# hail-met-v1.net
KiCad netlist of a schematic drawn in EAGLE
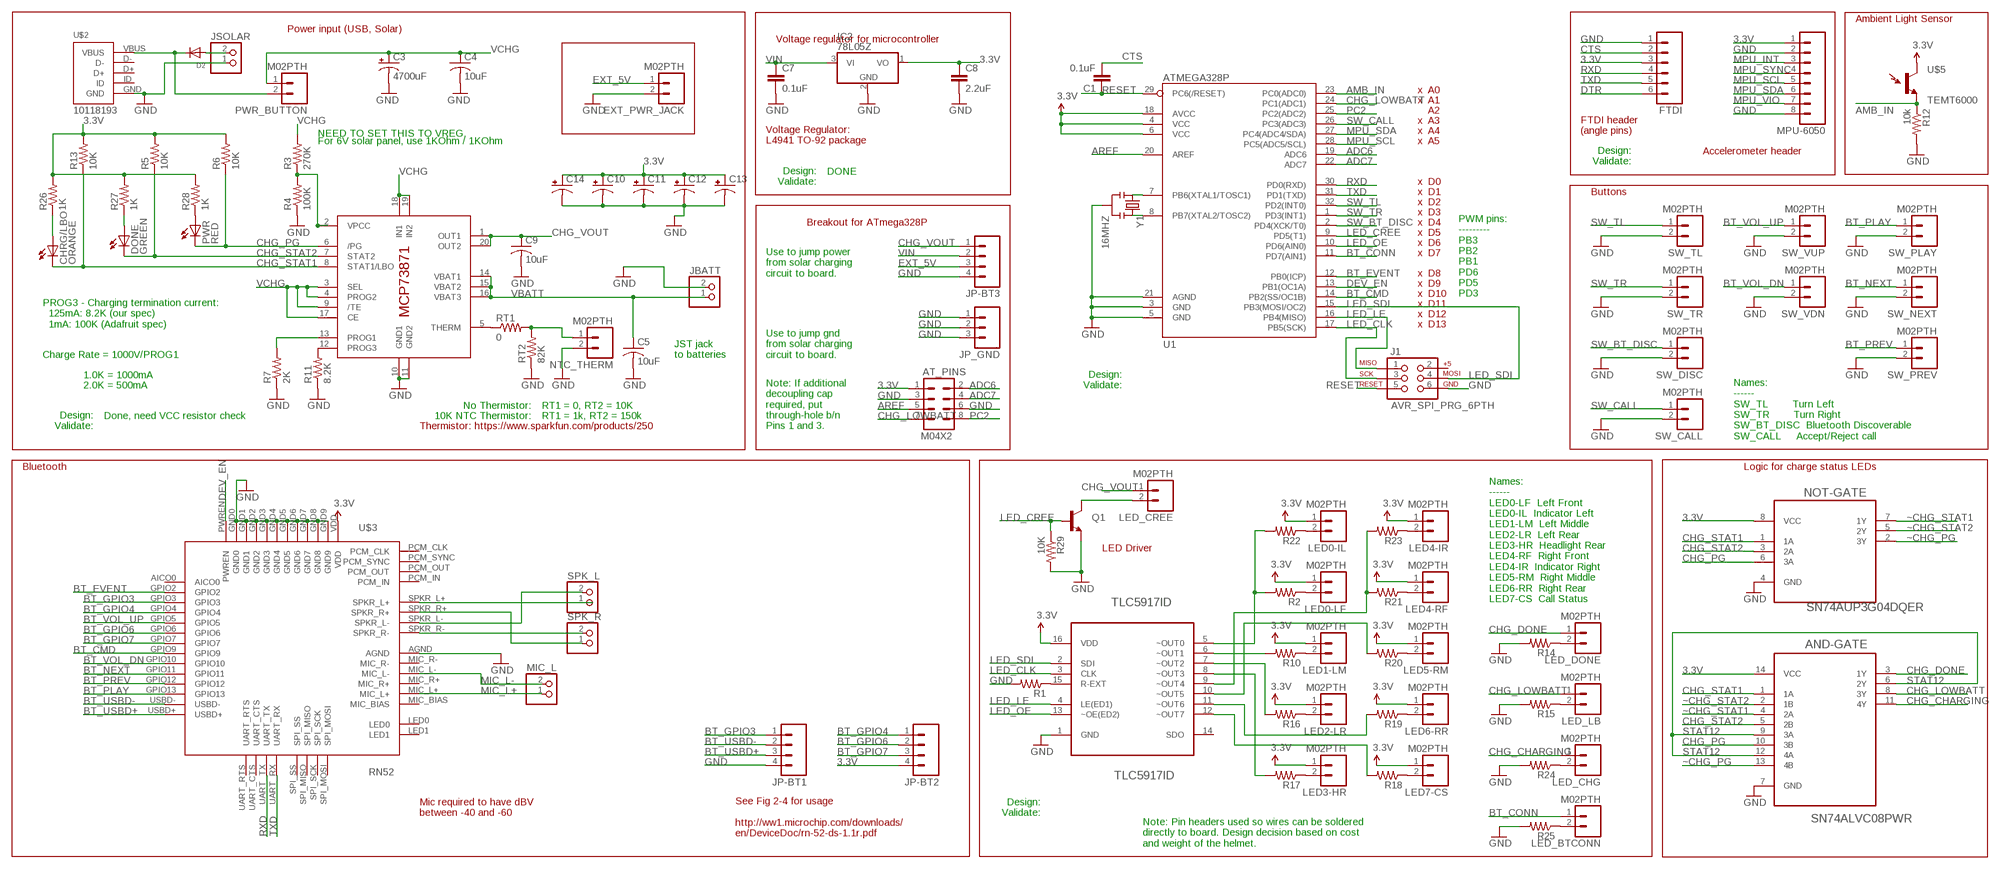
[diagram p0: schematic, sheet 1]

(export (version "E")
  (design (tool "Eeschema 10.0.6"))
  (components
    (comp (ref "AND-GATE")
      (value "SN74ALVC08PWR")
      (footprint "eagle-import:SOP65P640X120-14N")
      (libsource (lib "eagle-import") (part "SN74ALVC08PWR"))
    )
    (comp (ref "AT_PINS")
      (value "M04X2")
      (footprint "eagle-import:2X4")
      (libsource (lib "eagle-import") (part "M04X2"))
    )
    (comp (ref "C1")
      (value "0.1uF")
      (footprint "eagle-import:0805")
      (libsource (lib "eagle-import") (part "CAP0805"))
    )
    (comp (ref "C3")
      (value "4700uF")
      (footprint "eagle-import:E5-13")
      (libsource (lib "eagle-import") (part "CPOL-USE5-13"))
    )
    (comp (ref "C4")
      (value "10uF")
      (footprint "eagle-import:C0805K")
      (libsource (lib "eagle-import") (part "C-USC0805K"))
    )
    (comp (ref "C5")
      (value "10uF")
      (footprint "eagle-import:C0805K")
      (libsource (lib "eagle-import") (part "rcl_C-USC0805K"))
    )
    (comp (ref "C7")
      (value "0.1uF")
      (footprint "eagle-import:0805")
      (libsource (lib "eagle-import") (part "CAP0805"))
    )
    (comp (ref "C8")
      (value "2.2uF")
      (footprint "eagle-import:0805")
      (libsource (lib "eagle-import") (part "CAP0805"))
    )
    (comp (ref "C9")
      (value "10uF")
      (footprint "eagle-import:C0805K")
      (libsource (lib "eagle-import") (part "C-USC0805K"))
    )
    (comp (ref "C10")
      (value "CAP_POLPTH1")
      (footprint "eagle-import:CPOL-RADIAL-100UF-25V")
      (libsource (lib "eagle-import") (part "CAP_POLPTH1"))
    )
    (comp (ref "C11")
      (value "CAP_POLPTH1")
      (footprint "eagle-import:CPOL-RADIAL-100UF-25V")
      (libsource (lib "eagle-import") (part "CAP_POLPTH1"))
    )
    (comp (ref "C12")
      (value "CAP_POLPTH1")
      (footprint "eagle-import:CPOL-RADIAL-100UF-25V")
      (libsource (lib "eagle-import") (part "CAP_POLPTH1"))
    )
    (comp (ref "C13")
      (value "CAP_POLPTH1")
      (footprint "eagle-import:CPOL-RADIAL-100UF-25V")
      (libsource (lib "eagle-import") (part "CAP_POLPTH1"))
    )
    (comp (ref "C14")
      (value "CAP_POLPTH1")
      (footprint "eagle-import:CPOL-RADIAL-100UF-25V")
      (libsource (lib "eagle-import") (part "CAP_POLPTH1"))
    )
    (comp (ref "CHRG/LBO")
      (value "ORANGE")
      (footprint "eagle-import:CHIP-LED0805")
      (libsource (lib "eagle-import") (part "LEDCHIP-LED0805"))
    )
    (comp (ref "D2")
      (value "DIODESOD-123")
      (footprint "eagle-import:SOD-123")
      (libsource (lib "eagle-import") (part "DIODESOD-123"))
    )
    (comp (ref "DONE")
      (value "GREEN")
      (footprint "eagle-import:CHIP-LED0805")
      (libsource (lib "eagle-import") (part "LEDCHIP-LED0805"))
    )
    (comp (ref "EXT_PWR_JACK")
      (value "M02PTH")
      (footprint "eagle-import:1X02")
      (libsource (lib "eagle-import") (part "M02PTH"))
    )
    (comp (ref "FTDI")
      (value "M06LOCK")
      (footprint "eagle-import:1X06_LOCK")
      (libsource (lib "eagle-import") (part "M06LOCK"))
    )
    (comp (ref "IC1")
      (value "MCP73871")
      (footprint "eagle-import:QFN20")
      (libsource (lib "eagle-import") (part "MCP73871"))
    )
    (comp (ref "IC2")
      (value "78L05Z")
      (footprint "eagle-import:TO92")
      (libsource (lib "eagle-import") (part "78ZL05"))
    )
    (comp (ref "J1")
      (value "AVR_SPI_PRG_6PTH")
      (footprint "eagle-import:2X3")
      (libsource (lib "eagle-import") (part "AVR_SPI_PRG_6PTH"))
    )
    (comp (ref "JBATT")
      (value "JST_2PIN-SMT")
      (footprint "eagle-import:JST-PH-2-SMT")
      (libsource (lib "eagle-import") (part "JST_2PIN-SMT"))
    )
    (comp (ref "JP-BT1")
      (value "M04LOCK")
      (footprint "eagle-import:1X04_LOCK")
      (libsource (lib "eagle-import") (part "M04LOCK"))
    )
    (comp (ref "JP-BT2")
      (value "M04LOCK")
      (footprint "eagle-import:1X04_LOCK")
      (libsource (lib "eagle-import") (part "M04LOCK"))
    )
    (comp (ref "JP-BT3")
      (value "M04LOCK")
      (footprint "eagle-import:1X04_LOCK")
      (libsource (lib "eagle-import") (part "M04LOCK"))
    )
    (comp (ref "JP_GND")
      (value "M03LOCK")
      (footprint "eagle-import:1X03_LOCK")
      (libsource (lib "eagle-import") (part "M03LOCK"))
    )
    (comp (ref "JSOLAR")
      (value "JST_2PIN-SMT")
      (footprint "eagle-import:JST-PH-2-SMT")
      (libsource (lib "eagle-import") (part "JST_2PIN-SMT"))
    )
    (comp (ref "LED0-IL")
      (value "M02PTH")
      (footprint "eagle-import:1X02")
      (libsource (lib "eagle-import") (part "M02PTH"))
    )
    (comp (ref "LED0-LF")
      (value "M02PTH")
      (footprint "eagle-import:1X02")
      (libsource (lib "eagle-import") (part "M02PTH"))
    )
    (comp (ref "LED1-LM")
      (value "M02PTH")
      (footprint "eagle-import:1X02")
      (libsource (lib "eagle-import") (part "M02PTH"))
    )
    (comp (ref "LED2-LR")
      (value "M02PTH")
      (footprint "eagle-import:1X02")
      (libsource (lib "eagle-import") (part "M02PTH"))
    )
    (comp (ref "LED3-HR")
      (value "M02PTH")
      (footprint "eagle-import:1X02")
      (libsource (lib "eagle-import") (part "M02PTH"))
    )
    (comp (ref "LED4-IR")
      (value "M02PTH")
      (footprint "eagle-import:1X02")
      (libsource (lib "eagle-import") (part "M02PTH"))
    )
    (comp (ref "LED4-RF")
      (value "M02PTH")
      (footprint "eagle-import:1X02")
      (libsource (lib "eagle-import") (part "M02PTH"))
    )
    (comp (ref "LED5-RM")
      (value "M02PTH")
      (footprint "eagle-import:1X02")
      (libsource (lib "eagle-import") (part "M02PTH"))
    )
    (comp (ref "LED6-RR")
      (value "M02PTH")
      (footprint "eagle-import:1X02")
      (libsource (lib "eagle-import") (part "M02PTH"))
    )
    (comp (ref "LED7-CS")
      (value "M02PTH")
      (footprint "eagle-import:1X02")
      (libsource (lib "eagle-import") (part "M02PTH"))
    )
    (comp (ref "LED_BTCONN")
      (value "M02PTH")
      (footprint "eagle-import:1X02")
      (libsource (lib "eagle-import") (part "M02PTH"))
    )
    (comp (ref "LED_CHG")
      (value "M02PTH")
      (footprint "eagle-import:1X02")
      (libsource (lib "eagle-import") (part "M02PTH"))
    )
    (comp (ref "LED_CREE")
      (value "M02PTH")
      (footprint "eagle-import:1X02")
      (libsource (lib "eagle-import") (part "M02PTH"))
    )
    (comp (ref "LED_DONE")
      (value "M02PTH")
      (footprint "eagle-import:1X02")
      (libsource (lib "eagle-import") (part "M02PTH"))
    )
    (comp (ref "LED_LB")
      (value "M02PTH")
      (footprint "eagle-import:1X02")
      (libsource (lib "eagle-import") (part "M02PTH"))
    )
    (comp (ref "MIC_L")
      (value "JST_2PIN-SMT")
      (footprint "eagle-import:JST-PH-2-SMT")
      (libsource (lib "eagle-import") (part "JST_2PIN-SMT"))
    )
    (comp (ref "MPU-6050")
      (value "M08LOCK")
      (footprint "eagle-import:1X08_LOCK")
      (libsource (lib "eagle-import") (part "M08LOCK"))
    )
    (comp (ref "NOT-GATE")
      (value "SN74AUP3G04DQER")
      (footprint "eagle-import:SON35P100X140X40-8N")
      (libsource (lib "eagle-import") (part "SN74AUP3G04DQER"))
    )
    (comp (ref "NTC_THERM")
      (value "M02PTH")
      (footprint "eagle-import:1X02")
      (libsource (lib "eagle-import") (part "M02PTH"))
    )
    (comp (ref "PWR")
      (value "RED")
      (footprint "eagle-import:CHIP-LED0805")
      (libsource (lib "eagle-import") (part "LEDCHIP-LED0805"))
    )
    (comp (ref "PWR_BUTTON")
      (value "M02PTH")
      (footprint "eagle-import:1X02")
      (libsource (lib "eagle-import") (part "M02PTH"))
    )
    (comp (ref "Q1")
      (value "TRANSISTOR_NPNSOT23-3")
      (footprint "eagle-import:SOT23-3")
      (libsource (lib "eagle-import") (part "TRANSISTOR_NPNSOT23-3"))
    )
    (comp (ref "R1")
      (value "RESISTOR0805-RES")
      (footprint "eagle-import:0805")
      (libsource (lib "eagle-import") (part "RESISTOR0805-RES"))
    )
    (comp (ref "R2")
      (value "RESISTOR0805-RES")
      (footprint "eagle-import:0805")
      (libsource (lib "eagle-import") (part "RESISTOR0805-RES"))
    )
    (comp (ref "R3")
      (value "270K")
      (footprint "eagle-import:0805")
      (libsource (lib "eagle-import") (part "RESISTOR0805-RES"))
    )
    (comp (ref "R4")
      (value "100K")
      (footprint "eagle-import:0805")
      (libsource (lib "eagle-import") (part "RESISTOR0805-RES"))
    )
    (comp (ref "R5")
      (value "10K")
      (footprint "eagle-import:0805")
      (libsource (lib "eagle-import") (part "RESISTOR0805-RES"))
    )
    (comp (ref "R6")
      (value "10K")
      (footprint "eagle-import:0805")
      (libsource (lib "eagle-import") (part "RESISTOR0805-RES"))
    )
    (comp (ref "R7")
      (value "2K")
      (footprint "eagle-import:0805")
      (libsource (lib "eagle-import") (part "RESISTOR0805-RES"))
    )
    (comp (ref "R10")
      (value "RESISTOR0805-RES")
      (footprint "eagle-import:0805")
      (libsource (lib "eagle-import") (part "RESISTOR0805-RES"))
    )
    (comp (ref "R11")
      (value "8.2K")
      (footprint "eagle-import:0805")
      (libsource (lib "eagle-import") (part "RESISTOR0805-RES"))
    )
    (comp (ref "R12")
      (value "10k")
      (footprint "eagle-import:0805")
      (libsource (lib "eagle-import") (part "RESISTOR0805-RES"))
    )
    (comp (ref "R13")
      (value "10K")
      (footprint "eagle-import:0805")
      (libsource (lib "eagle-import") (part "RESISTOR0805-RES"))
    )
    (comp (ref "R14")
      (value "RESISTOR0805-RES")
      (footprint "eagle-import:0805")
      (libsource (lib "eagle-import") (part "RESISTOR0805-RES"))
    )
    (comp (ref "R15")
      (value "RESISTOR0805-RES")
      (footprint "eagle-import:0805")
      (libsource (lib "eagle-import") (part "RESISTOR0805-RES"))
    )
    (comp (ref "R16")
      (value "RESISTOR0805-RES")
      (footprint "eagle-import:0805")
      (libsource (lib "eagle-import") (part "RESISTOR0805-RES"))
    )
    (comp (ref "R17")
      (value "RESISTOR0805-RES")
      (footprint "eagle-import:0805")
      (libsource (lib "eagle-import") (part "RESISTOR0805-RES"))
    )
    (comp (ref "R18")
      (value "RESISTOR0805-RES")
      (footprint "eagle-import:0805")
      (libsource (lib "eagle-import") (part "RESISTOR0805-RES"))
    )
    (comp (ref "R19")
      (value "RESISTOR0805-RES")
      (footprint "eagle-import:0805")
      (libsource (lib "eagle-import") (part "RESISTOR0805-RES"))
    )
    (comp (ref "R20")
      (value "RESISTOR0805-RES")
      (footprint "eagle-import:0805")
      (libsource (lib "eagle-import") (part "RESISTOR0805-RES"))
    )
    (comp (ref "R21")
      (value "RESISTOR0805-RES")
      (footprint "eagle-import:0805")
      (libsource (lib "eagle-import") (part "RESISTOR0805-RES"))
    )
    (comp (ref "R22")
      (value "RESISTOR0805-RES")
      (footprint "eagle-import:0805")
      (libsource (lib "eagle-import") (part "RESISTOR0805-RES"))
    )
    (comp (ref "R23")
      (value "RESISTOR0805-RES")
      (footprint "eagle-import:0805")
      (libsource (lib "eagle-import") (part "RESISTOR0805-RES"))
    )
    (comp (ref "R24")
      (value "RESISTOR0805-RES")
      (footprint "eagle-import:0805")
      (libsource (lib "eagle-import") (part "RESISTOR0805-RES"))
    )
    (comp (ref "R25")
      (value "RESISTOR0805-RES")
      (footprint "eagle-import:0805")
      (libsource (lib "eagle-import") (part "RESISTOR0805-RES"))
    )
    (comp (ref "R26")
      (value "1K")
      (footprint "eagle-import:0805")
      (libsource (lib "eagle-import") (part "RESISTOR0805-RES"))
    )
    (comp (ref "R27")
      (value "1K")
      (footprint "eagle-import:0805")
      (libsource (lib "eagle-import") (part "RESISTOR0805-RES"))
    )
    (comp (ref "R28")
      (value "1K")
      (footprint "eagle-import:0805")
      (libsource (lib "eagle-import") (part "RESISTOR0805-RES"))
    )
    (comp (ref "R29")
      (value "10K")
      (footprint "eagle-import:0805")
      (libsource (lib "eagle-import") (part "RESISTOR0805-RES"))
    )
    (comp (ref "RT1")
      (value "0")
      (footprint "eagle-import:0805")
      (libsource (lib "eagle-import") (part "RESISTOR0805-RES"))
    )
    (comp (ref "RT2")
      (value "82K")
      (footprint "eagle-import:0805")
      (libsource (lib "eagle-import") (part "RESISTOR0805-RES"))
    )
    (comp (ref "SPK_L")
      (value "JST_2PIN-SMT")
      (footprint "eagle-import:JST-PH-2-SMT")
      (libsource (lib "eagle-import") (part "JST_2PIN-SMT"))
    )
    (comp (ref "SPK_R")
      (value "JST_2PIN-SMT")
      (footprint "eagle-import:JST-PH-2-SMT")
      (libsource (lib "eagle-import") (part "JST_2PIN-SMT"))
    )
    (comp (ref "SW_CALL")
      (value "M02PTH")
      (footprint "eagle-import:1X02")
      (libsource (lib "eagle-import") (part "M02PTH"))
    )
    (comp (ref "SW_DISC")
      (value "M02PTH")
      (footprint "eagle-import:1X02")
      (libsource (lib "eagle-import") (part "M02PTH"))
    )
    (comp (ref "SW_NEXT")
      (value "M02PTH")
      (footprint "eagle-import:1X02")
      (libsource (lib "eagle-import") (part "M02PTH"))
    )
    (comp (ref "SW_PLAY")
      (value "M02PTH")
      (footprint "eagle-import:1X02")
      (libsource (lib "eagle-import") (part "M02PTH"))
    )
    (comp (ref "SW_PREV")
      (value "M02PTH")
      (footprint "eagle-import:1X02")
      (libsource (lib "eagle-import") (part "M02PTH"))
    )
    (comp (ref "SW_TL")
      (value "M02PTH")
      (footprint "eagle-import:1X02")
      (libsource (lib "eagle-import") (part "M02PTH"))
    )
    (comp (ref "SW_TR")
      (value "M02PTH")
      (footprint "eagle-import:1X02")
      (libsource (lib "eagle-import") (part "M02PTH"))
    )
    (comp (ref "SW_VDN")
      (value "M02PTH")
      (footprint "eagle-import:1X02")
      (libsource (lib "eagle-import") (part "M02PTH"))
    )
    (comp (ref "SW_VUP")
      (value "M02PTH")
      (footprint "eagle-import:1X02")
      (libsource (lib "eagle-import") (part "M02PTH"))
    )
    (comp (ref "TLC5917ID")
      (value "TLC5917ID")
      (footprint "eagle-import:SOIC127P600X175-16N")
      (libsource (lib "eagle-import") (part "TLC5917ID"))
    )
    (comp (ref "U$2")
      (value "10118193")
      (footprint "eagle-import:10118193")
      (libsource (lib "eagle-import") (part "10118193"))
    )
    (comp (ref "U$3")
      (value "RN52")
      (footprint "eagle-import:RN52")
      (libsource (lib "eagle-import") (part "RN52"))
    )
    (comp (ref "U$5")
      (value "TEMT6000")
      (footprint "eagle-import:TEMT6000-SEN")
      (libsource (lib "eagle-import") (part "TEMT6000"))
    )
    (comp (ref "U1")
      (value "ATMEGA328P")
      (footprint "eagle-import:TQFP32-08")
      (libsource (lib "eagle-import") (part "ATMEGA328_SMT"))
    )
    (comp (ref "Y1")
      (value "16MHZ")
      (footprint "eagle-import:RESONATOR-SMD")
      (libsource (lib "eagle-import") (part "RESONATOR16MHZ"))
    )
  )
  (nets
    (net (code "1") (name "/ADC6") (class "Default")
      (node (ref "AT_PINS") (pin "2") (pinfunction "2_2") (pintype "passive"))
      (node (ref "U1") (pin "19") (pinfunction "ADC6_19") (pintype "bidirectional"))
    )
    (net (code "2") (name "/ADC7") (class "Default")
      (node (ref "AT_PINS") (pin "4") (pinfunction "4_4") (pintype "passive"))
      (node (ref "U1") (pin "22") (pinfunction "ADC7_22") (pintype "bidirectional"))
    )
    (net (code "3") (name "/AMB_IN") (class "Default")
      (node (ref "R12") (pin "1") (pinfunction "1_1") (pintype "passive"))
      (node (ref "U$5") (pin "EMITTER") (pinfunction "E1_EMITTER") (pintype "passive"))
      (node (ref "U1") (pin "23") (pinfunction "PC0(ADC0)_23") (pintype "bidirectional"))
    )
    (net (code "4") (name "/AREF") (class "Default")
      (node (ref "AT_PINS") (pin "5") (pinfunction "5_5") (pintype "passive"))
      (node (ref "U1") (pin "20") (pinfunction "AREF_20") (pintype "bidirectional"))
    )
    (net (code "5") (name "/BT_CMD") (class "Default")
      (node (ref "U$3") (pin "GPIO9") (pinfunction "GPIO9_GPIO9") (pintype "bidirectional"))
      (node (ref "U1") (pin "14") (pinfunction "PB2(SS/OC1B)_14") (pintype "bidirectional"))
    )
    (net (code "6") (name "/BT_CONN") (class "Default")
      (node (ref "LED_BTCONN") (pin "1") (pinfunction "1_1") (pintype "passive"))
      (node (ref "U1") (pin "11") (pinfunction "PD7(AIN1)_11") (pintype "bidirectional"))
    )
    (net (code "7") (name "/BT_EVENT") (class "Default")
      (node (ref "U$3") (pin "GPIO2") (pinfunction "GPIO2_GPIO2") (pintype "bidirectional"))
      (node (ref "U1") (pin "12") (pinfunction "PB0(ICP)_12") (pintype "bidirectional"))
    )
    (net (code "8") (name "/BT_GPIO3") (class "Default")
      (node (ref "JP-BT1") (pin "1") (pinfunction "1_1") (pintype "passive"))
      (node (ref "U$3") (pin "GPIO3") (pinfunction "GPIO3_GPIO3") (pintype "bidirectional"))
    )
    (net (code "9") (name "/BT_GPIO4") (class "Default")
      (node (ref "JP-BT2") (pin "1") (pinfunction "1_1") (pintype "passive"))
      (node (ref "U$3") (pin "GPIO4") (pinfunction "GPIO4_GPIO4") (pintype "bidirectional"))
    )
    (net (code "10") (name "/BT_GPIO6") (class "Default")
      (node (ref "JP-BT2") (pin "2") (pinfunction "2_2") (pintype "passive"))
      (node (ref "U$3") (pin "GPIO6") (pinfunction "GPIO6_GPIO6") (pintype "bidirectional"))
    )
    (net (code "11") (name "/BT_GPIO7") (class "Default")
      (node (ref "JP-BT2") (pin "3") (pinfunction "3_3") (pintype "passive"))
      (node (ref "U$3") (pin "GPIO7") (pinfunction "GPIO7_GPIO7") (pintype "bidirectional"))
    )
    (net (code "12") (name "/BT_NEXT") (class "Default")
      (node (ref "SW_NEXT") (pin "1") (pinfunction "1_1") (pintype "passive"))
      (node (ref "U$3") (pin "GPIO11") (pinfunction "GPIO11_GPIO11") (pintype "bidirectional"))
    )
    (net (code "13") (name "/BT_PLAY") (class "Default")
      (node (ref "SW_PLAY") (pin "1") (pinfunction "1_1") (pintype "passive"))
      (node (ref "U$3") (pin "GPIO13") (pinfunction "GPIO13_GPIO13") (pintype "bidirectional"))
    )
    (net (code "14") (name "/BT_PREV") (class "Default")
      (node (ref "SW_PREV") (pin "1") (pinfunction "1_1") (pintype "passive"))
      (node (ref "U$3") (pin "GPIO12") (pinfunction "GPIO12_GPIO12") (pintype "bidirectional"))
    )
    (net (code "15") (name "/BT_USBD+") (class "Default")
      (node (ref "JP-BT1") (pin "3") (pinfunction "3_3") (pintype "passive"))
      (node (ref "U$3") (pin "USBD+") (pinfunction "USBD+_USBD+") (pintype "bidirectional"))
    )
    (net (code "16") (name "/BT_USBD-") (class "Default")
      (node (ref "JP-BT1") (pin "2") (pinfunction "2_2") (pintype "passive"))
      (node (ref "U$3") (pin "USBD-") (pinfunction "USBD-_USBD-") (pintype "bidirectional"))
    )
    (net (code "17") (name "/BT_VOL_DN") (class "Default")
      (node (ref "SW_VDN") (pin "1") (pinfunction "1_1") (pintype "passive"))
      (node (ref "U$3") (pin "GPIO10") (pinfunction "GPIO10_GPIO10") (pintype "bidirectional"))
    )
    (net (code "18") (name "/BT_VOL_UP") (class "Default")
      (node (ref "SW_VUP") (pin "1") (pinfunction "1_1") (pintype "passive"))
      (node (ref "U$3") (pin "GPIO5") (pinfunction "GPIO5_GPIO5") (pintype "bidirectional"))
    )
    (net (code "19") (name "/CHG_CHARGING") (class "Default")
      (node (ref "AND-GATE") (pin "11") (pinfunction "4Y_11") (pintype "output"))
      (node (ref "LED_CHG") (pin "1") (pinfunction "1_1") (pintype "passive"))
    )
    (net (code "20") (name "/CHG_DONE") (class "Default")
      (node (ref "AND-GATE") (pin "3") (pinfunction "1Y_3") (pintype "output"))
      (node (ref "LED_DONE") (pin "1") (pinfunction "1_1") (pintype "passive"))
    )
    (net (code "21") (name "/CHG_LOWBATT") (class "Default")
      (node (ref "AND-GATE") (pin "8") (pinfunction "3Y_8") (pintype "output"))
      (node (ref "AT_PINS") (pin "7") (pinfunction "7_7") (pintype "passive"))
      (node (ref "LED_LB") (pin "1") (pinfunction "1_1") (pintype "passive"))
      (node (ref "U1") (pin "24") (pinfunction "PC1(ADC1)_24") (pintype "bidirectional"))
    )
    (net (code "22") (name "/CHG_PG") (class "Default")
      (node (ref "AND-GATE") (pin "10") (pinfunction "3B_10") (pintype "input"))
      (node (ref "IC1") (pin "6") (pinfunction "/PG_6") (pintype "output"))
      (node (ref "NOT-GATE") (pin "6") (pinfunction "3A_6") (pintype "input"))
      (node (ref "PWR") (pin "C") (pinfunction "C_C") (pintype "passive"))
      (node (ref "R6") (pin "1") (pinfunction "1_1") (pintype "passive"))
    )
    (net (code "23") (name "/CHG_STAT1") (class "Default")
      (node (ref "AND-GATE") (pin "1") (pinfunction "1A_1") (pintype "input"))
      (node (ref "CHRG/LBO") (pin "C") (pinfunction "C_C") (pintype "passive"))
      (node (ref "IC1") (pin "8") (pinfunction "STAT1/LBO_8") (pintype "output"))
      (node (ref "NOT-GATE") (pin "1") (pinfunction "1A_1") (pintype "input"))
      (node (ref "R13") (pin "1") (pinfunction "1_1") (pintype "passive"))
    )
    (net (code "24") (name "/CHG_STAT2") (class "Default")
      (node (ref "AND-GATE") (pin "5") (pinfunction "2B_5") (pintype "input"))
      (node (ref "DONE") (pin "C") (pinfunction "C_C") (pintype "passive"))
      (node (ref "IC1") (pin "7") (pinfunction "STAT2_7") (pintype "output"))
      (node (ref "NOT-GATE") (pin "3") (pinfunction "2A_3") (pintype "input"))
      (node (ref "R5") (pin "1") (pinfunction "1_1") (pintype "passive"))
    )
    (net (code "25") (name "/CHG_VOUT") (class "Default")
      (node (ref "C9") (pin "1") (pinfunction "1_1") (pintype "passive"))
      (node (ref "IC1") (pin "1") (pinfunction "OUT1_1") (pintype "output"))
      (node (ref "IC1") (pin "20") (pinfunction "OUT2_20") (pintype "output"))
      (node (ref "JP-BT3") (pin "1") (pinfunction "1_1") (pintype "passive"))
      (node (ref "LED_CREE") (pin "1") (pinfunction "1_1") (pintype "passive"))
    )
    (net (code "26") (name "/CTS") (class "Default")
      (node (ref "C1") (pin "2") (pinfunction "2_2") (pintype "passive"))
      (node (ref "FTDI") (pin "2") (pinfunction "2_2") (pintype "passive"))
    )
    (net (code "27") (name "/DEV_EN") (class "Default")
      (node (ref "U$3") (pin "PWREN") (pinfunction "PWREN_PWREN") (pintype "bidirectional"))
      (node (ref "U1") (pin "13") (pinfunction "PB1(OC1A)_13") (pintype "bidirectional"))
    )
    (net (code "28") (name "/DTR") (class "Default")
      (node (ref "FTDI") (pin "6") (pinfunction "6_6") (pintype "passive"))
    )
    (net (code "29") (name "/EXT_5V") (class "Default")
      (node (ref "EXT_PWR_JACK") (pin "1") (pinfunction "1_1") (pintype "passive"))
      (node (ref "JP-BT3") (pin "3") (pinfunction "3_3") (pintype "passive"))
    )
    (net (code "30") (name "/LED_CLK") (class "Default")
      (node (ref "J1") (pin "3") (pinfunction "3_3") (pintype "passive"))
      (node (ref "TLC5917ID") (pin "3") (pinfunction "CLK_3") (pintype "input"))
      (node (ref "U1") (pin "17") (pinfunction "PB5(SCK)_17") (pintype "bidirectional"))
    )
    (net (code "31") (name "/LED_CREE") (class "Default")
      (node (ref "Q1") (pin "1") (pinfunction "B_1") (pintype "passive"))
      (node (ref "R29") (pin "1") (pinfunction "1_1") (pintype "passive"))
      (node (ref "U1") (pin "9") (pinfunction "PD5(T1)_9") (pintype "bidirectional"))
    )
    (net (code "32") (name "/LED_LE") (class "Default")
      (node (ref "J1") (pin "1") (pinfunction "1_1") (pintype "passive"))
      (node (ref "TLC5917ID") (pin "4") (pinfunction "LE(ED1)_4") (pintype "input"))
      (node (ref "U1") (pin "16") (pinfunction "PB4(MISO)_16") (pintype "bidirectional"))
    )
    (net (code "33") (name "/LED_OE") (class "Default")
      (node (ref "TLC5917ID") (pin "13") (pinfunction "~{OE(ED2})_13") (pintype "input"))
      (node (ref "U1") (pin "10") (pinfunction "PD6(AIN0)_10") (pintype "bidirectional"))
    )
    (net (code "34") (name "/LED_SDI") (class "Default")
      (node (ref "J1") (pin "4") (pinfunction "4_4") (pintype "passive"))
      (node (ref "TLC5917ID") (pin "2") (pinfunction "SDI_2") (pintype "input"))
      (node (ref "U1") (pin "15") (pinfunction "PB3(MOSI/OC2)_15") (pintype "bidirectional"))
    )
    (net (code "35") (name "/MIC_L+") (class "Default")
      (node (ref "MIC_L") (pin "1") (pinfunction "2_1") (pintype "passive"))
      (node (ref "U$3") (pin "MIC_L+") (pinfunction "MIC_L+_MIC_L+") (pintype "bidirectional"))
    )
    (net (code "36") (name "/MIC_L-") (class "Default")
      (node (ref "MIC_L") (pin "2") (pinfunction "1_2") (pintype "passive"))
      (node (ref "U$3") (pin "MIC_L-") (pinfunction "MIC_L-_MIC_L-") (pintype "bidirectional"))
    )
    (net (code "37") (name "/MPU_INT") (class "Default")
      (node (ref "MPU-6050") (pin "3") (pinfunction "3_3") (pintype "passive"))
    )
    (net (code "38") (name "/MPU_SCL") (class "Default")
      (node (ref "MPU-6050") (pin "5") (pinfunction "5_5") (pintype "passive"))
      (node (ref "U1") (pin "28") (pinfunction "PC5(ADC5/SCL)_28") (pintype "bidirectional"))
    )
    (net (code "39") (name "/MPU_SDA") (class "Default")
      (node (ref "MPU-6050") (pin "6") (pinfunction "6_6") (pintype "passive"))
      (node (ref "U1") (pin "27") (pinfunction "PC4(ADC4/SDA)_27") (pintype "bidirectional"))
    )
    (net (code "40") (name "/MPU_SYNC") (class "Default")
      (node (ref "MPU-6050") (pin "4") (pinfunction "4_4") (pintype "passive"))
    )
    (net (code "41") (name "/MPU_VIO") (class "Default")
      (node (ref "MPU-6050") (pin "7") (pinfunction "7_7") (pintype "passive"))
    )
    (net (code "42") (name "/PC2") (class "Default")
      (node (ref "AT_PINS") (pin "8") (pinfunction "8_8") (pintype "passive"))
      (node (ref "U1") (pin "25") (pinfunction "PC2(ADC2)_25") (pintype "bidirectional"))
    )
    (net (code "43") (name "/RESET") (class "Default")
      (node (ref "C1") (pin "1") (pinfunction "1_1") (pintype "passive"))
      (node (ref "J1") (pin "5") (pinfunction "5_5") (pintype "passive"))
      (node (ref "U1") (pin "29") (pinfunction "PC6(/RESET)_29") (pintype "bidirectional"))
    )
    (net (code "44") (name "/RXD") (class "Default")
      (node (ref "FTDI") (pin "4") (pinfunction "4_4") (pintype "passive"))
      (node (ref "U$3") (pin "UART_TX") (pinfunction "UART_TX_UART_TX") (pintype "bidirectional"))
      (node (ref "U1") (pin "30") (pinfunction "PD0(RXD)_30") (pintype "bidirectional"))
    )
    (net (code "45") (name "/STAT12") (class "Default")
      (node (ref "AND-GATE") (pin "12") (pinfunction "4A_12") (pintype "input"))
      (node (ref "AND-GATE") (pin "6") (pinfunction "2Y_6") (pintype "output"))
      (node (ref "AND-GATE") (pin "9") (pinfunction "3A_9") (pintype "input"))
    )
    (net (code "46") (name "/SW_BT_DISC") (class "Default")
      (node (ref "SW_DISC") (pin "1") (pinfunction "1_1") (pintype "passive"))
      (node (ref "U1") (pin "2") (pinfunction "PD4(XCK/T0)_2") (pintype "bidirectional"))
    )
    (net (code "47") (name "/SW_CALL") (class "Default")
      (node (ref "SW_CALL") (pin "1") (pinfunction "1_1") (pintype "passive"))
      (node (ref "U1") (pin "26") (pinfunction "PC3(ADC3)_26") (pintype "bidirectional"))
    )
    (net (code "48") (name "/SW_TL") (class "Default")
      (node (ref "SW_TL") (pin "1") (pinfunction "1_1") (pintype "passive"))
      (node (ref "U1") (pin "32") (pinfunction "PD2(INT0)_32") (pintype "bidirectional"))
    )
    (net (code "49") (name "/SW_TR") (class "Default")
      (node (ref "SW_TR") (pin "1") (pinfunction "1_1") (pintype "passive"))
      (node (ref "U1") (pin "1") (pinfunction "PD3(INT1)_1") (pintype "bidirectional"))
    )
    (net (code "50") (name "/TXD") (class "Default")
      (node (ref "FTDI") (pin "5") (pinfunction "5_5") (pintype "passive"))
      (node (ref "U$3") (pin "UART_RX") (pinfunction "UART_RX_UART_RX") (pintype "bidirectional"))
      (node (ref "U1") (pin "31") (pinfunction "PD1(TXD)_31") (pintype "bidirectional"))
    )
    (net (code "51") (name "/VBATT") (class "Default")
      (node (ref "C5") (pin "1") (pinfunction "1_1") (pintype "passive"))
      (node (ref "IC1") (pin "14") (pinfunction "VBAT1_14") (pintype "output"))
      (node (ref "IC1") (pin "15") (pinfunction "VBAT2_15") (pintype "output"))
      (node (ref "IC1") (pin "16") (pinfunction "VBAT3_16") (pintype "output"))
      (node (ref "JBATT") (pin "1") (pinfunction "2_1") (pintype "passive"))
    )
    (net (code "52") (name "/VCHG") (class "Default")
      (node (ref "C3") (pin "+") (pinfunction "+_+") (pintype "passive"))
      (node (ref "C4") (pin "1") (pinfunction "1_1") (pintype "passive"))
      (node (ref "IC1") (pin "17") (pinfunction "CE_17") (pintype "input"))
      (node (ref "IC1") (pin "18") (pinfunction "IN1_18") (pintype "input"))
      (node (ref "IC1") (pin "19") (pinfunction "IN2_19") (pintype "input"))
      (node (ref "IC1") (pin "3") (pinfunction "SEL_3") (pintype "input"))
      (node (ref "IC1") (pin "4") (pinfunction "PROG2_4") (pintype "input"))
      (node (ref "IC1") (pin "9") (pinfunction "/TE_9") (pintype "input"))
      (node (ref "PWR_BUTTON") (pin "1") (pinfunction "1_1") (pintype "passive"))
      (node (ref "R3") (pin "2") (pinfunction "2_2") (pintype "passive"))
    )
    (net (code "53") (name "/VIN") (class "Default")
      (node (ref "C7") (pin "1") (pinfunction "1_1") (pintype "passive"))
      (node (ref "IC2") (pin "3") (pinfunction "VI_3") (pintype "input"))
      (node (ref "JP-BT3") (pin "2") (pinfunction "2_2") (pintype "passive"))
    )
    (net (code "54") (name "/~{CHG_PG}") (class "Default")
      (node (ref "AND-GATE") (pin "13") (pinfunction "4B_13") (pintype "input"))
      (node (ref "NOT-GATE") (pin "2") (pinfunction "3Y_2") (pintype "output"))
    )
    (net (code "55") (name "/~{CHG_STAT1}") (class "Default")
      (node (ref "AND-GATE") (pin "4") (pinfunction "2A_4") (pintype "input"))
      (node (ref "NOT-GATE") (pin "7") (pinfunction "1Y_7") (pintype "output"))
    )
    (net (code "56") (name "/~{CHG_STAT2}") (class "Default")
      (node (ref "AND-GATE") (pin "2") (pinfunction "1B_2") (pintype "input"))
      (node (ref "NOT-GATE") (pin "5") (pinfunction "2Y_5") (pintype "output"))
    )
    (net (code "57") (name "3.3V") (class "Default")
      (node (ref "AND-GATE") (pin "14") (pinfunction "VCC_14") (pintype "power_in"))
      (node (ref "AT_PINS") (pin "1") (pinfunction "1_1") (pintype "passive"))
      (node (ref "C10") (pin "1") (pinfunction "+_1") (pintype "passive"))
      (node (ref "C11") (pin "1") (pinfunction "+_1") (pintype "passive"))
      (node (ref "C12") (pin "1") (pinfunction "+_1") (pintype "passive"))
      (node (ref "C13") (pin "1") (pinfunction "+_1") (pintype "passive"))
      (node (ref "C14") (pin "1") (pinfunction "+_1") (pintype "passive"))
      (node (ref "C8") (pin "1") (pinfunction "1_1") (pintype "passive"))
      (node (ref "FTDI") (pin "3") (pinfunction "3_3") (pintype "passive"))
      (node (ref "IC2") (pin "1") (pinfunction "VO_1") (pintype "passive"))
      (node (ref "JP-BT2") (pin "4") (pinfunction "4_4") (pintype "passive"))
      (node (ref "LED0-IL") (pin "1") (pinfunction "1_1") (pintype "passive"))
      (node (ref "LED0-LF") (pin "1") (pinfunction "1_1") (pintype "passive"))
      (node (ref "LED1-LM") (pin "1") (pinfunction "1_1") (pintype "passive"))
      (node (ref "LED2-LR") (pin "1") (pinfunction "1_1") (pintype "passive"))
      (node (ref "LED3-HR") (pin "1") (pinfunction "1_1") (pintype "passive"))
      (node (ref "LED4-IR") (pin "1") (pinfunction "1_1") (pintype "passive"))
      (node (ref "LED4-RF") (pin "1") (pinfunction "1_1") (pintype "passive"))
      (node (ref "LED5-RM") (pin "1") (pinfunction "1_1") (pintype "passive"))
      (node (ref "LED6-RR") (pin "1") (pinfunction "1_1") (pintype "passive"))
      (node (ref "LED7-CS") (pin "1") (pinfunction "1_1") (pintype "passive"))
      (node (ref "MPU-6050") (pin "1") (pinfunction "1_1") (pintype "passive"))
      (node (ref "NOT-GATE") (pin "8") (pinfunction "VCC_8") (pintype "power_in"))
      (node (ref "R13") (pin "2") (pinfunction "2_2") (pintype "passive"))
      (node (ref "R26") (pin "2") (pinfunction "2_2") (pintype "passive"))
      (node (ref "R27") (pin "2") (pinfunction "2_2") (pintype "passive"))
      (node (ref "R28") (pin "2") (pinfunction "2_2") (pintype "passive"))
      (node (ref "R5") (pin "2") (pinfunction "2_2") (pintype "passive"))
      (node (ref "R6") (pin "2") (pinfunction "2_2") (pintype "passive"))
      (node (ref "TLC5917ID") (pin "16") (pinfunction "VDD_16") (pintype "power_in"))
      (node (ref "U$3") (pin "VDD") (pinfunction "VDD_VDD") (pintype "bidirectional"))
      (node (ref "U$5") (pin "COLLECTOR") (pinfunction "C1_COLLECTOR") (pintype "passive"))
      (node (ref "U1") (pin "18") (pinfunction "AVCC_18") (pintype "bidirectional"))
      (node (ref "U1") (pin "4") (pinfunction "VCC_4") (pintype "bidirectional"))
      (node (ref "U1") (pin "6") (pinfunction "VCC_6") (pintype "bidirectional"))
    )
    (net (code "58") (name "GND") (class "Default")
      (node (ref "AND-GATE") (pin "7") (pinfunction "GND_7") (pintype "passive"))
      (node (ref "AT_PINS") (pin "3") (pinfunction "3_3") (pintype "passive"))
      (node (ref "AT_PINS") (pin "6") (pinfunction "6_6") (pintype "passive"))
      (node (ref "C10") (pin "2") (pinfunction "-_2") (pintype "passive"))
      (node (ref "C11") (pin "2") (pinfunction "-_2") (pintype "passive"))
      (node (ref "C12") (pin "2") (pinfunction "-_2") (pintype "passive"))
      (node (ref "C13") (pin "2") (pinfunction "-_2") (pintype "passive"))
      (node (ref "C14") (pin "2") (pinfunction "-_2") (pintype "passive"))
      (node (ref "C3") (pin "-") (pinfunction "-_-") (pintype "passive"))
      (node (ref "C4") (pin "2") (pinfunction "2_2") (pintype "passive"))
      (node (ref "C5") (pin "2") (pinfunction "2_2") (pintype "passive"))
      (node (ref "C7") (pin "2") (pinfunction "2_2") (pintype "passive"))
      (node (ref "C8") (pin "2") (pinfunction "2_2") (pintype "passive"))
      (node (ref "C9") (pin "2") (pinfunction "2_2") (pintype "passive"))
      (node (ref "EXT_PWR_JACK") (pin "2") (pinfunction "2_2") (pintype "passive"))
      (node (ref "FTDI") (pin "1") (pinfunction "1_1") (pintype "passive"))
      (node (ref "IC1") (pin "10") (pinfunction "GND1_10") (pintype "power_in"))
      (node (ref "IC1") (pin "11") (pinfunction "GND2_11") (pintype "power_in"))
      (node (ref "IC2") (pin "2") (pinfunction "GND_2") (pintype "passive"))
      (node (ref "J1") (pin "6") (pinfunction "6_6") (pintype "passive"))
      (node (ref "JBATT") (pin "2") (pinfunction "1_2") (pintype "passive"))
      (node (ref "JP-BT1") (pin "4") (pinfunction "4_4") (pintype "passive"))
      (node (ref "JP-BT3") (pin "4") (pinfunction "4_4") (pintype "passive"))
      (node (ref "JP_GND") (pin "1") (pinfunction "1_1") (pintype "passive"))
      (node (ref "JP_GND") (pin "2") (pinfunction "2_2") (pintype "passive"))
      (node (ref "JP_GND") (pin "3") (pinfunction "3_3") (pintype "passive"))
      (node (ref "JSOLAR") (pin "1") (pinfunction "2_1") (pintype "passive"))
      (node (ref "MPU-6050") (pin "2") (pinfunction "2_2") (pintype "passive"))
      (node (ref "MPU-6050") (pin "8") (pinfunction "8_8") (pintype "passive"))
      (node (ref "NOT-GATE") (pin "4") (pinfunction "GND_4") (pintype "passive"))
      (node (ref "NTC_THERM") (pin "2") (pinfunction "2_2") (pintype "passive"))
      (node (ref "Q1") (pin "2") (pinfunction "E_2") (pintype "passive"))
      (node (ref "R1") (pin "2") (pinfunction "2_2") (pintype "passive"))
      (node (ref "R11") (pin "1") (pinfunction "1_1") (pintype "passive"))
      (node (ref "R12") (pin "2") (pinfunction "2_2") (pintype "passive"))
      (node (ref "R14") (pin "2") (pinfunction "2_2") (pintype "passive"))
      (node (ref "R15") (pin "2") (pinfunction "2_2") (pintype "passive"))
      (node (ref "R24") (pin "2") (pinfunction "2_2") (pintype "passive"))
      (node (ref "R25") (pin "2") (pinfunction "2_2") (pintype "passive"))
      (node (ref "R29") (pin "2") (pinfunction "2_2") (pintype "passive"))
      (node (ref "R4") (pin "1") (pinfunction "1_1") (pintype "passive"))
      (node (ref "R7") (pin "1") (pinfunction "1_1") (pintype "passive"))
      (node (ref "RT2") (pin "1") (pinfunction "1_1") (pintype "passive"))
      (node (ref "SW_CALL") (pin "2") (pinfunction "2_2") (pintype "passive"))
      (node (ref "SW_DISC") (pin "2") (pinfunction "2_2") (pintype "passive"))
      (node (ref "SW_NEXT") (pin "2") (pinfunction "2_2") (pintype "passive"))
      (node (ref "SW_PLAY") (pin "2") (pinfunction "2_2") (pintype "passive"))
      (node (ref "SW_PREV") (pin "2") (pinfunction "2_2") (pintype "passive"))
      (node (ref "SW_TL") (pin "2") (pinfunction "2_2") (pintype "passive"))
      (node (ref "SW_TR") (pin "2") (pinfunction "2_2") (pintype "passive"))
      (node (ref "SW_VDN") (pin "2") (pinfunction "2_2") (pintype "passive"))
      (node (ref "SW_VUP") (pin "2") (pinfunction "2_2") (pintype "passive"))
      (node (ref "TLC5917ID") (pin "1") (pinfunction "GND_1") (pintype "passive"))
      (node (ref "U$2") (pin "GND") (pinfunction "GND_GND") (pintype "bidirectional"))
      (node (ref "U$3") (pin "AGND") (pinfunction "AGND_AGND") (pintype "bidirectional"))
      (node (ref "U$3") (pin "GND0") (pinfunction "GND0_GND0") (pintype "bidirectional"))
      (node (ref "U$3") (pin "GND1") (pinfunction "GND1_GND1") (pintype "bidirectional"))
      (node (ref "U$3") (pin "GND2") (pinfunction "GND2_GND2") (pintype "bidirectional"))
      (node (ref "U$3") (pin "GND3") (pinfunction "GND3_GND3") (pintype "bidirectional"))
      (node (ref "U$3") (pin "GND4") (pinfunction "GND4_GND4") (pintype "bidirectional"))
      (node (ref "U$3") (pin "GND5") (pinfunction "GND5_GND5") (pintype "bidirectional"))
      (node (ref "U$3") (pin "GND6") (pinfunction "GND6_GND6") (pintype "bidirectional"))
      (node (ref "U$3") (pin "GND7") (pinfunction "GND7_GND7") (pintype "bidirectional"))
      (node (ref "U$3") (pin "GND8") (pinfunction "GND8_GND8") (pintype "bidirectional"))
      (node (ref "U$3") (pin "GND9") (pinfunction "GND9_GND9") (pintype "bidirectional"))
      (node (ref "U1") (pin "21") (pinfunction "AGND_21") (pintype "bidirectional"))
      (node (ref "U1") (pin "3") (pinfunction "GND_3") (pintype "bidirectional"))
      (node (ref "U1") (pin "5") (pinfunction "GND_5") (pintype "bidirectional"))
      (node (ref "Y1") (pin "2") (pinfunction "2_2") (pintype "passive"))
    )
    (net (code "59") (name "Net-(CHRG/LBO-PadA)") (class "Default")
      (node (ref "CHRG/LBO") (pin "A") (pinfunction "A_A") (pintype "passive"))
      (node (ref "R26") (pin "1") (pinfunction "1_1") (pintype "passive"))
    )
    (net (code "60") (name "Net-(D2-PadC)") (class "Default")
      (node (ref "D2") (pin "C") (pinfunction "C_C") (pintype "passive"))
      (node (ref "PWR_BUTTON") (pin "2") (pinfunction "2_2") (pintype "passive"))
      (node (ref "U$2") (pin "VBUS") (pinfunction "VBUS_VBUS") (pintype "bidirectional"))
    )
    (net (code "61") (name "Net-(DONE-PadA)") (class "Default")
      (node (ref "DONE") (pin "A") (pinfunction "A_A") (pintype "passive"))
      (node (ref "R27") (pin "1") (pinfunction "1_1") (pintype "passive"))
    )
    (net (code "62") (name "Net-(IC1-PROG1)") (class "Default")
      (node (ref "IC1") (pin "13") (pinfunction "PROG1_13") (pintype "input"))
      (node (ref "R7") (pin "2") (pinfunction "2_2") (pintype "passive"))
    )
    (net (code "63") (name "Net-(IC1-PROG3)") (class "Default")
      (node (ref "IC1") (pin "12") (pinfunction "PROG3_12") (pintype "input"))
      (node (ref "R11") (pin "2") (pinfunction "2_2") (pintype "passive"))
    )
    (net (code "64") (name "Net-(IC1-THERM)") (class "Default")
      (node (ref "IC1") (pin "5") (pinfunction "THERM_5") (pintype "input"))
      (node (ref "RT1") (pin "1") (pinfunction "1_1") (pintype "passive"))
    )
    (net (code "65") (name "Net-(IC1-VPCC)") (class "Default")
      (node (ref "IC1") (pin "2") (pinfunction "VPCC_2") (pintype "input"))
      (node (ref "R3") (pin "1") (pinfunction "1_1") (pintype "passive"))
      (node (ref "R4") (pin "2") (pinfunction "2_2") (pintype "passive"))
    )
    (net (code "66") (name "Net-(JSOLAR-1)") (class "Default")
      (node (ref "D2") (pin "A") (pinfunction "A_A") (pintype "passive"))
      (node (ref "JSOLAR") (pin "2") (pinfunction "1_2") (pintype "passive"))
    )
    (net (code "67") (name "Net-(LED0-IL-Pad2)") (class "Default")
      (node (ref "LED0-IL") (pin "2") (pinfunction "2_2") (pintype "passive"))
      (node (ref "R22") (pin "1") (pinfunction "1_1") (pintype "passive"))
    )
    (net (code "68") (name "Net-(LED0-LF-Pad2)") (class "Default")
      (node (ref "LED0-LF") (pin "2") (pinfunction "2_2") (pintype "passive"))
      (node (ref "R2") (pin "1") (pinfunction "1_1") (pintype "passive"))
    )
    (net (code "69") (name "Net-(LED1-LM-Pad2)") (class "Default")
      (node (ref "LED1-LM") (pin "2") (pinfunction "2_2") (pintype "passive"))
      (node (ref "R10") (pin "1") (pinfunction "1_1") (pintype "passive"))
    )
    (net (code "70") (name "Net-(LED2-LR-Pad2)") (class "Default")
      (node (ref "LED2-LR") (pin "2") (pinfunction "2_2") (pintype "passive"))
      (node (ref "R16") (pin "1") (pinfunction "1_1") (pintype "passive"))
    )
    (net (code "71") (name "Net-(LED3-HR-Pad2)") (class "Default")
      (node (ref "LED3-HR") (pin "2") (pinfunction "2_2") (pintype "passive"))
      (node (ref "R17") (pin "1") (pinfunction "1_1") (pintype "passive"))
    )
    (net (code "72") (name "Net-(LED4-IR-Pad2)") (class "Default")
      (node (ref "LED4-IR") (pin "2") (pinfunction "2_2") (pintype "passive"))
      (node (ref "R23") (pin "1") (pinfunction "1_1") (pintype "passive"))
    )
    (net (code "73") (name "Net-(LED4-RF-Pad2)") (class "Default")
      (node (ref "LED4-RF") (pin "2") (pinfunction "2_2") (pintype "passive"))
      (node (ref "R21") (pin "1") (pinfunction "1_1") (pintype "passive"))
    )
    (net (code "74") (name "Net-(LED5-RM-Pad2)") (class "Default")
      (node (ref "LED5-RM") (pin "2") (pinfunction "2_2") (pintype "passive"))
      (node (ref "R20") (pin "1") (pinfunction "1_1") (pintype "passive"))
    )
    (net (code "75") (name "Net-(LED6-RR-Pad2)") (class "Default")
      (node (ref "LED6-RR") (pin "2") (pinfunction "2_2") (pintype "passive"))
      (node (ref "R19") (pin "1") (pinfunction "1_1") (pintype "passive"))
    )
    (net (code "76") (name "Net-(LED7-CS-Pad2)") (class "Default")
      (node (ref "LED7-CS") (pin "2") (pinfunction "2_2") (pintype "passive"))
      (node (ref "R18") (pin "1") (pinfunction "1_1") (pintype "passive"))
    )
    (net (code "77") (name "Net-(LED_BTCONN-Pad2)") (class "Default")
      (node (ref "LED_BTCONN") (pin "2") (pinfunction "2_2") (pintype "passive"))
      (node (ref "R25") (pin "1") (pinfunction "1_1") (pintype "passive"))
    )
    (net (code "78") (name "Net-(LED_CHG-Pad2)") (class "Default")
      (node (ref "LED_CHG") (pin "2") (pinfunction "2_2") (pintype "passive"))
      (node (ref "R24") (pin "1") (pinfunction "1_1") (pintype "passive"))
    )
    (net (code "79") (name "Net-(LED_DONE-Pad2)") (class "Default")
      (node (ref "LED_DONE") (pin "2") (pinfunction "2_2") (pintype "passive"))
      (node (ref "R14") (pin "1") (pinfunction "1_1") (pintype "passive"))
    )
    (net (code "80") (name "Net-(LED_LB-Pad2)") (class "Default")
      (node (ref "LED_LB") (pin "2") (pinfunction "2_2") (pintype "passive"))
      (node (ref "R15") (pin "1") (pinfunction "1_1") (pintype "passive"))
    )
    (net (code "81") (name "Net-(NTC_THERM-Pad1)") (class "Default")
      (node (ref "NTC_THERM") (pin "1") (pinfunction "1_1") (pintype "passive"))
      (node (ref "RT1") (pin "2") (pinfunction "2_2") (pintype "passive"))
      (node (ref "RT2") (pin "2") (pinfunction "2_2") (pintype "passive"))
    )
    (net (code "82") (name "Net-(PWR-PadA)") (class "Default")
      (node (ref "PWR") (pin "A") (pinfunction "A_A") (pintype "passive"))
      (node (ref "R28") (pin "1") (pinfunction "1_1") (pintype "passive"))
    )
    (net (code "83") (name "Net-(Q1-C)") (class "Default")
      (node (ref "LED_CREE") (pin "2") (pinfunction "2_2") (pintype "passive"))
      (node (ref "Q1") (pin "3") (pinfunction "C_3") (pintype "passive"))
    )
    (net (code "84") (name "Net-(SPK_L-1)") (class "Default")
      (node (ref "SPK_L") (pin "2") (pinfunction "1_2") (pintype "passive"))
      (node (ref "U$3") (pin "SPKR_L-") (pinfunction "SPKR_L-_SPKR_L-") (pintype "bidirectional"))
    )
    (net (code "85") (name "Net-(SPK_R-1)") (class "Default")
      (node (ref "SPK_R") (pin "2") (pinfunction "1_2") (pintype "passive"))
      (node (ref "U$3") (pin "SPKR_R-") (pinfunction "SPKR_R-_SPKR_R-") (pintype "bidirectional"))
    )
    (net (code "86") (name "Net-(SPK_R-2)") (class "Default")
      (node (ref "SPK_R") (pin "1") (pinfunction "2_1") (pintype "passive"))
      (node (ref "U$3") (pin "SPKR_R+") (pinfunction "SPKR_R+_SPKR_R+") (pintype "bidirectional"))
    )
    (net (code "87") (name "Net-(TLC5917ID-R-EXT)") (class "Default")
      (node (ref "R1") (pin "1") (pinfunction "1_1") (pintype "passive"))
      (node (ref "TLC5917ID") (pin "15") (pinfunction "R-EXT_15") (pintype "passive"))
    )
    (net (code "88") (name "Net-(TLC5917ID-~{OUT0})") (class "Default")
      (node (ref "R2") (pin "2") (pinfunction "2_2") (pintype "passive"))
      (node (ref "R22") (pin "2") (pinfunction "2_2") (pintype "passive"))
      (node (ref "TLC5917ID") (pin "5") (pinfunction "~{OUT0}_5") (pintype "output"))
    )
    (net (code "89") (name "Net-(TLC5917ID-~{OUT1})") (class "Default")
      (node (ref "R10") (pin "2") (pinfunction "2_2") (pintype "passive"))
      (node (ref "TLC5917ID") (pin "6") (pinfunction "~{OUT1}_6") (pintype "output"))
    )
    (net (code "90") (name "Net-(TLC5917ID-~{OUT2})") (class "Default")
      (node (ref "R16") (pin "2") (pinfunction "2_2") (pintype "passive"))
      (node (ref "TLC5917ID") (pin "7") (pinfunction "~{OUT2}_7") (pintype "output"))
    )
    (net (code "91") (name "Net-(TLC5917ID-~{OUT3})") (class "Default")
      (node (ref "R17") (pin "2") (pinfunction "2_2") (pintype "passive"))
      (node (ref "TLC5917ID") (pin "8") (pinfunction "~{OUT3}_8") (pintype "output"))
    )
    (net (code "92") (name "Net-(TLC5917ID-~{OUT4})") (class "Default")
      (node (ref "R21") (pin "2") (pinfunction "2_2") (pintype "passive"))
      (node (ref "R23") (pin "2") (pinfunction "2_2") (pintype "passive"))
      (node (ref "TLC5917ID") (pin "9") (pinfunction "~{OUT4}_9") (pintype "output"))
    )
    (net (code "93") (name "Net-(TLC5917ID-~{OUT5})") (class "Default")
      (node (ref "R20") (pin "2") (pinfunction "2_2") (pintype "passive"))
      (node (ref "TLC5917ID") (pin "10") (pinfunction "~{OUT5}_10") (pintype "output"))
    )
    (net (code "94") (name "Net-(TLC5917ID-~{OUT6})") (class "Default")
      (node (ref "R19") (pin "2") (pinfunction "2_2") (pintype "passive"))
      (node (ref "TLC5917ID") (pin "11") (pinfunction "~{OUT6}_11") (pintype "output"))
    )
    (net (code "95") (name "Net-(TLC5917ID-~{OUT7})") (class "Default")
      (node (ref "R18") (pin "2") (pinfunction "2_2") (pintype "passive"))
      (node (ref "TLC5917ID") (pin "12") (pinfunction "~{OUT7}_12") (pintype "output"))
    )
    (net (code "96") (name "Net-(U1-PB6(XTAL1{slash}TOSC1))") (class "Default")
      (node (ref "U1") (pin "7") (pinfunction "PB6(XTAL1/TOSC1)_7") (pintype "bidirectional"))
      (node (ref "Y1") (pin "1") (pinfunction "1_1") (pintype "passive"))
    )
    (net (code "97") (name "Net-(U1-PB7(XTAL2{slash}TOSC2))") (class "Default")
      (node (ref "U1") (pin "8") (pinfunction "PB7(XTAL2/TOSC2)_8") (pintype "bidirectional"))
      (node (ref "Y1") (pin "3") (pinfunction "3_3") (pintype "passive"))
    )
    (net (code "98") (name "unconnected-(J1-Pad2)") (class "Default")
      (node (ref "J1") (pin "2") (pinfunction "2_2") (pintype "passive"))
    )
    (net (code "99") (name "unconnected-(SPK_L-2-Pad1)") (class "Default")
      (node (ref "SPK_L") (pin "1") (pinfunction "2_1") (pintype "passive"))
    )
    (net (code "100") (name "unconnected-(TLC5917ID-SDO-Pad14)") (class "Default")
      (node (ref "TLC5917ID") (pin "14") (pinfunction "SDO_14") (pintype "output"))
    )
    (net (code "101") (name "unconnected-(U$2-PadD+)") (class "Default")
      (node (ref "U$2") (pin "D+") (pinfunction "D+_D+") (pintype "bidirectional"))
    )
    (net (code "102") (name "unconnected-(U$2-PadD-)") (class "Default")
      (node (ref "U$2") (pin "D-") (pinfunction "D-_D-") (pintype "bidirectional"))
    )
    (net (code "103") (name "unconnected-(U$2-PadID)") (class "Default")
      (node (ref "U$2") (pin "ID") (pinfunction "ID_ID") (pintype "bidirectional"))
    )
    (net (code "104") (name "unconnected-(U$3-PadAICO0)") (class "Default")
      (node (ref "U$3") (pin "AICO0") (pinfunction "AICO0_AICO0") (pintype "bidirectional"))
    )
    (net (code "105") (name "unconnected-(U$3-PadLED0)") (class "Default")
      (node (ref "U$3") (pin "LED0") (pinfunction "LED0_LED0") (pintype "bidirectional"))
    )
    (net (code "106") (name "unconnected-(U$3-PadLED1)") (class "Default")
      (node (ref "U$3") (pin "LED1") (pinfunction "LED1_LED1") (pintype "bidirectional"))
    )
    (net (code "107") (name "unconnected-(U$3-PadMIC_BIAS)") (class "Default")
      (node (ref "U$3") (pin "MIC_BIAS") (pinfunction "MIC_BIAS_MIC_BIAS") (pintype "bidirectional"))
    )
    (net (code "108") (name "unconnected-(U$3-PadMIC_R+)") (class "Default")
      (node (ref "U$3") (pin "MIC_R+") (pinfunction "MIC_R+_MIC_R+") (pintype "bidirectional"))
    )
    (net (code "109") (name "unconnected-(U$3-PadMIC_R-)") (class "Default")
      (node (ref "U$3") (pin "MIC_R-") (pinfunction "MIC_R-_MIC_R-") (pintype "bidirectional"))
    )
    (net (code "110") (name "unconnected-(U$3-PadPCM_CLK)") (class "Default")
      (node (ref "U$3") (pin "PCM_CLK") (pinfunction "PCM_CLK_PCM_CLK") (pintype "bidirectional"))
    )
    (net (code "111") (name "unconnected-(U$3-PadPCM_IN)") (class "Default")
      (node (ref "U$3") (pin "PCM_IN") (pinfunction "PCM_IN_PCM_IN") (pintype "bidirectional"))
    )
    (net (code "112") (name "unconnected-(U$3-PadPCM_OUT)") (class "Default")
      (node (ref "U$3") (pin "PCM_OUT") (pinfunction "PCM_OUT_PCM_OUT") (pintype "bidirectional"))
    )
    (net (code "113") (name "unconnected-(U$3-PadPCM_SYNC)") (class "Default")
      (node (ref "U$3") (pin "PCM_SYNC") (pinfunction "PCM_SYNC_PCM_SYNC") (pintype "bidirectional"))
    )
    (net (code "114") (name "unconnected-(U$3-PadSPI_MISO)") (class "Default")
      (node (ref "U$3") (pin "SPI_MISO") (pinfunction "SPI_MISO_SPI_MISO") (pintype "bidirectional"))
    )
    (net (code "115") (name "unconnected-(U$3-PadSPI_MOSI)") (class "Default")
      (node (ref "U$3") (pin "SPI_MOSI") (pinfunction "SPI_MOSI_SPI_MOSI") (pintype "bidirectional"))
    )
    (net (code "116") (name "unconnected-(U$3-PadSPI_SCK)") (class "Default")
      (node (ref "U$3") (pin "SPI_SCK") (pinfunction "SPI_SCK_SPI_SCK") (pintype "bidirectional"))
    )
    (net (code "117") (name "unconnected-(U$3-PadSPI_SS)") (class "Default")
      (node (ref "U$3") (pin "SPI_SS") (pinfunction "SPI_SS_SPI_SS") (pintype "bidirectional"))
    )
    (net (code "118") (name "unconnected-(U$3-PadSPKR_L+)") (class "Default")
      (node (ref "U$3") (pin "SPKR_L+") (pinfunction "SPKR_L+_SPKR_L+") (pintype "bidirectional"))
    )
    (net (code "119") (name "unconnected-(U$3-PadUART_CTS)") (class "Default")
      (node (ref "U$3") (pin "UART_CTS") (pinfunction "UART_CTS_UART_CTS") (pintype "bidirectional"))
    )
    (net (code "120") (name "unconnected-(U$3-PadUART_RTS)") (class "Default")
      (node (ref "U$3") (pin "UART_RTS") (pinfunction "UART_RTS_UART_RTS") (pintype "bidirectional"))
    )
  )
)
